# robot_vr.net
KiCad netlist of a schematic drawn in EAGLE
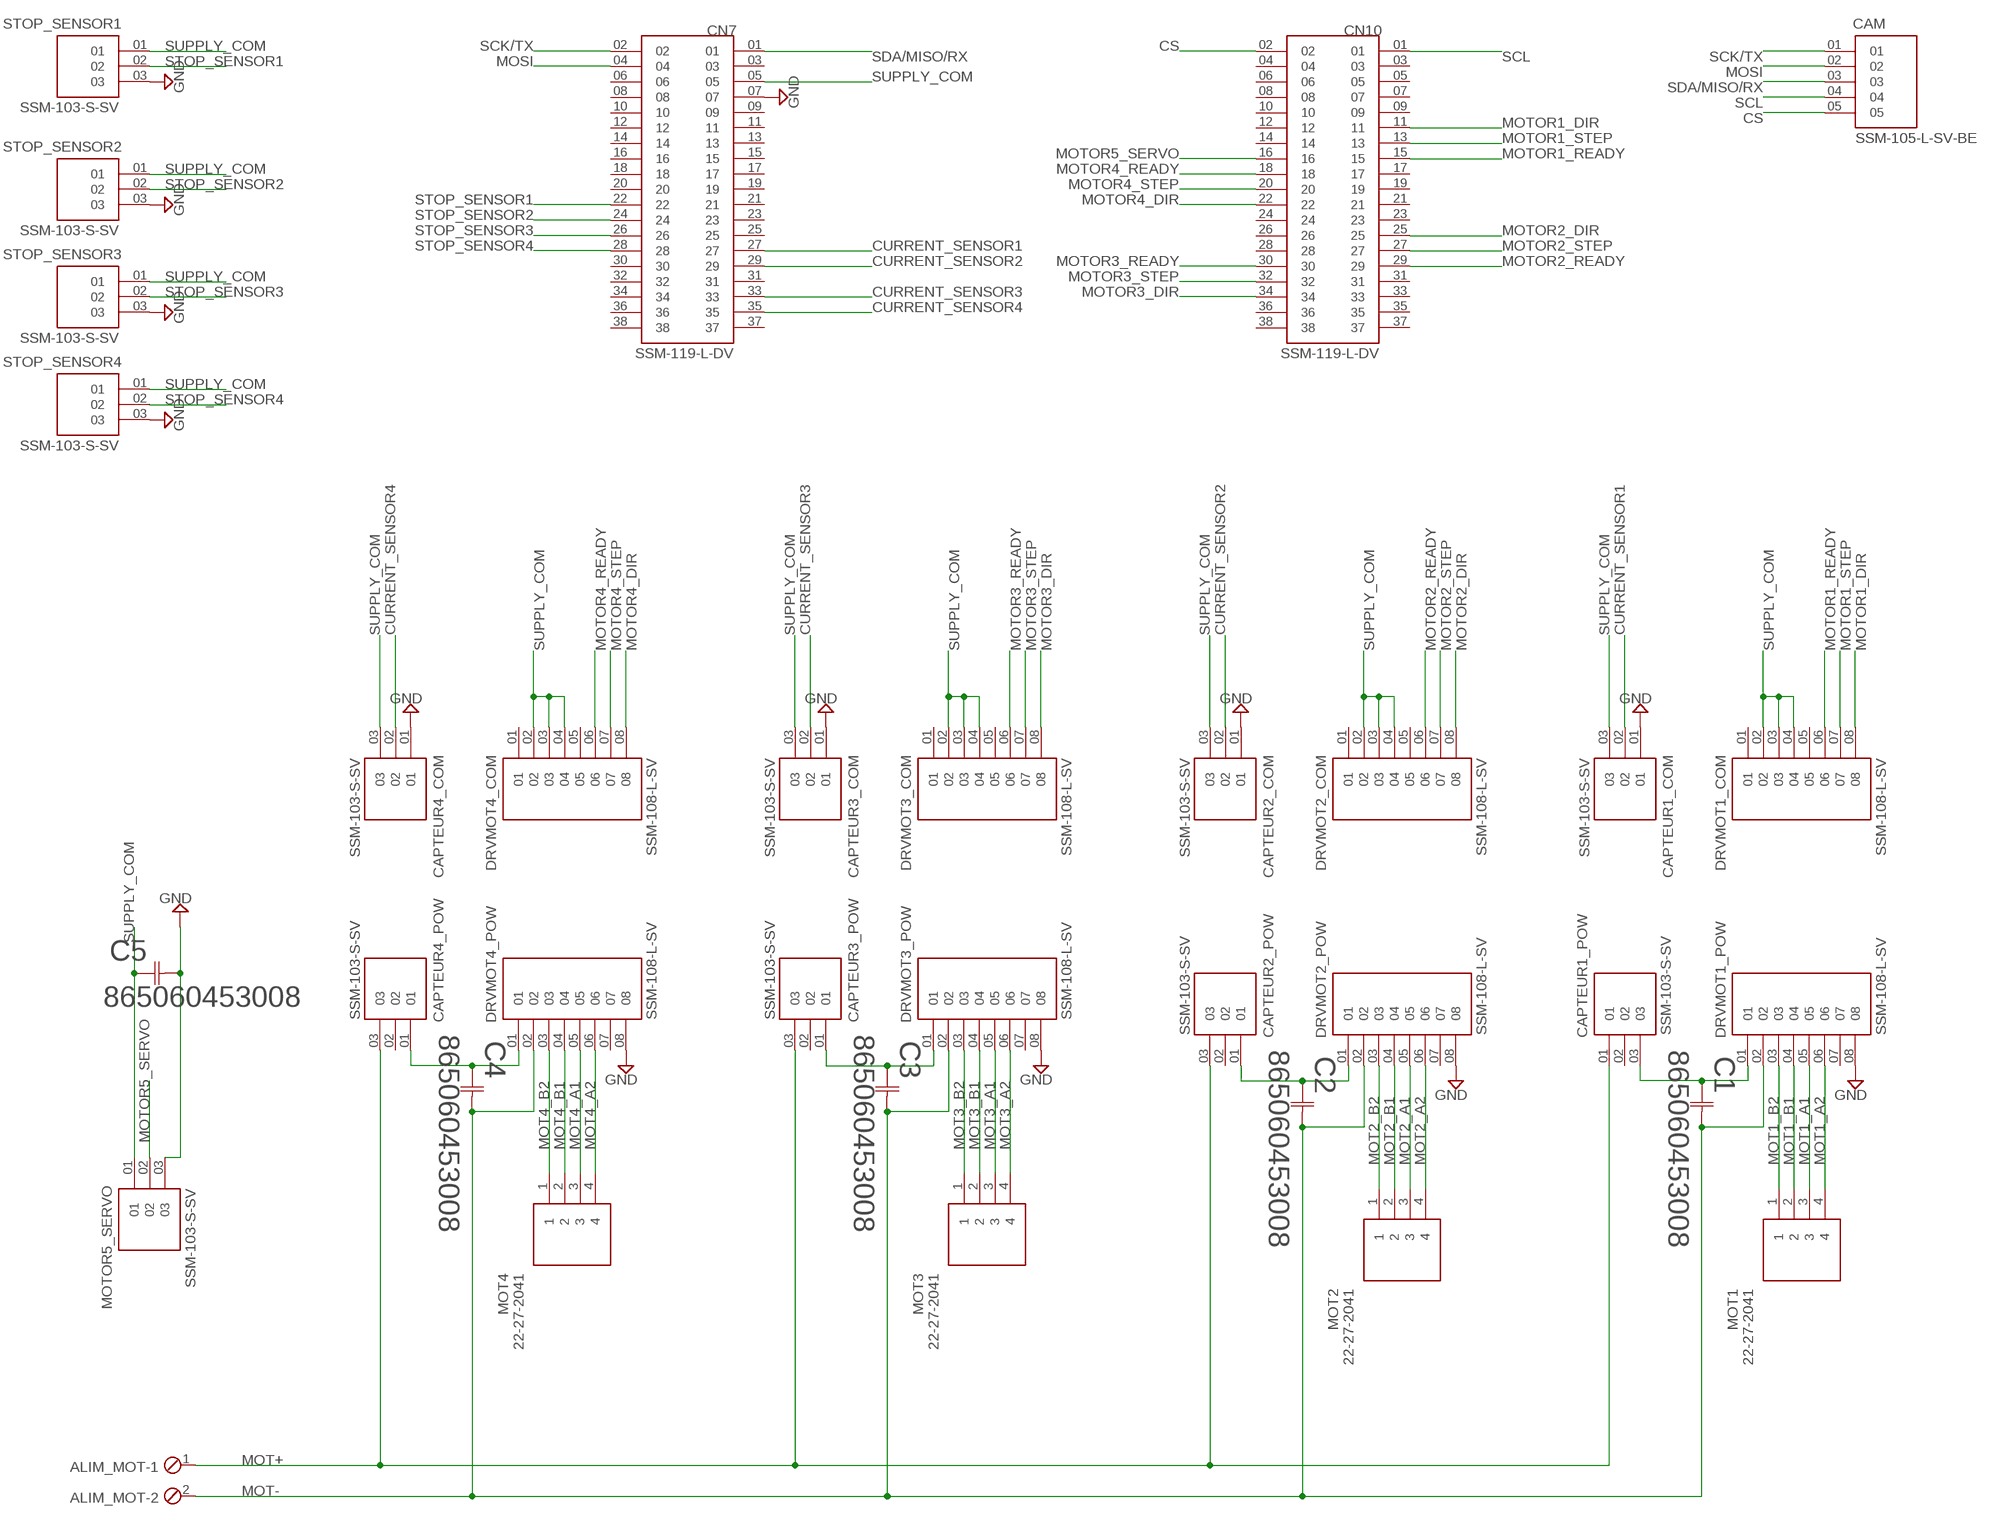
[diagram p0: schematic, sheet 1]

(export (version "E")
  (design (tool "Eeschema 10.0.6"))
  (components
    (comp (ref "ALIM_MOT")
      (value "MPT2")
      (footprint "eagle-import:2POL254")
      (libsource (lib "eagle-import") (part "MPT2"))
    )
    (comp (ref "C1")
      (value "865060453008")
      (footprint "eagle-import:CAP_865060453008_WRE")
      (fields (field (name "COPYRIGHT") "Copyright (C) 2022 Ultra Librarian. All rights reserved."))
      (libsource (lib "eagle-import") (part "865060453008"))
    )
    (comp (ref "C2")
      (value "865060453008")
      (footprint "eagle-import:CAP_865060453008_WRE")
      (fields (field (name "COPYRIGHT") "Copyright (C) 2022 Ultra Librarian. All rights reserved."))
      (libsource (lib "eagle-import") (part "865060453008"))
    )
    (comp (ref "C3")
      (value "865060453008")
      (footprint "eagle-import:CAP_865060453008_WRE")
      (fields (field (name "COPYRIGHT") "Copyright (C) 2022 Ultra Librarian. All rights reserved."))
      (libsource (lib "eagle-import") (part "865060453008"))
    )
    (comp (ref "C4")
      (value "865060453008")
      (footprint "eagle-import:CAP_865060453008_WRE")
      (fields (field (name "COPYRIGHT") "Copyright (C) 2022 Ultra Librarian. All rights reserved."))
      (libsource (lib "eagle-import") (part "865060453008"))
    )
    (comp (ref "C5")
      (value "865060453008")
      (footprint "eagle-import:CAP_865060453008_WRE")
      (fields (field (name "COPYRIGHT") "Copyright (C) 2022 Ultra Librarian. All rights reserved."))
      (libsource (lib "eagle-import") (part "865060453008"))
    )
    (comp (ref "CAM")
      (value "SSM-105-L-SV-BE")
      (footprint "eagle-import:SAMTEC_SSM-105-L-SV-BE")
      (fields (field (name "MF") "Samtec") (field (name "MP") "SSM-105-L-SV-BE-TR"))
      (libsource (lib "eagle-import") (part "SSM-105-L-SV-BE"))
    )
    (comp (ref "CAPTEUR1_COM")
      (value "SSM-103-S-SV")
      (footprint "eagle-import:SAMTEC_SSM-103-S-SV")
      (fields (field (name "MF") "Samtec"))
      (libsource (lib "eagle-import") (part "SSM-103-S-SV"))
    )
    (comp (ref "CAPTEUR1_POW")
      (value "SSM-103-S-SV")
      (footprint "eagle-import:SAMTEC_SSM-103-S-SV")
      (fields (field (name "MF") "Samtec"))
      (libsource (lib "eagle-import") (part "SSM-103-S-SV"))
    )
    (comp (ref "CAPTEUR2_COM")
      (value "SSM-103-S-SV")
      (footprint "eagle-import:SAMTEC_SSM-103-S-SV")
      (fields (field (name "MF") "Samtec"))
      (libsource (lib "eagle-import") (part "SSM-103-S-SV"))
    )
    (comp (ref "CAPTEUR2_POW")
      (value "SSM-103-S-SV")
      (footprint "eagle-import:SAMTEC_SSM-103-S-SV")
      (fields (field (name "MF") "Samtec"))
      (libsource (lib "eagle-import") (part "SSM-103-S-SV"))
    )
    (comp (ref "CAPTEUR3_COM")
      (value "SSM-103-S-SV")
      (footprint "eagle-import:SAMTEC_SSM-103-S-SV")
      (fields (field (name "MF") "Samtec"))
      (libsource (lib "eagle-import") (part "SSM-103-S-SV"))
    )
    (comp (ref "CAPTEUR3_POW")
      (value "SSM-103-S-SV")
      (footprint "eagle-import:SAMTEC_SSM-103-S-SV")
      (fields (field (name "MF") "Samtec"))
      (libsource (lib "eagle-import") (part "SSM-103-S-SV"))
    )
    (comp (ref "CAPTEUR4_COM")
      (value "SSM-103-S-SV")
      (footprint "eagle-import:SAMTEC_SSM-103-S-SV")
      (fields (field (name "MF") "Samtec"))
      (libsource (lib "eagle-import") (part "SSM-103-S-SV"))
    )
    (comp (ref "CAPTEUR4_POW")
      (value "SSM-103-S-SV")
      (footprint "eagle-import:SAMTEC_SSM-103-S-SV")
      (fields (field (name "MF") "Samtec"))
      (libsource (lib "eagle-import") (part "SSM-103-S-SV"))
    )
    (comp (ref "CN7")
      (value "SSM-119-L-DV")
      (footprint "eagle-import:SAMTEC_SSM-119-L-DV")
      (fields (field (name "MF") "Samtec Inc."))
      (libsource (lib "eagle-import") (part "SSM-119-L-DV"))
    )
    (comp (ref "CN10")
      (value "SSM-119-L-DV")
      (footprint "eagle-import:SAMTEC_SSM-119-L-DV")
      (fields (field (name "MF") "Samtec Inc."))
      (libsource (lib "eagle-import") (part "SSM-119-L-DV"))
    )
    (comp (ref "DRVMOT1_COM")
      (value "SSM-108-L-SV")
      (footprint "eagle-import:SAMTEC_SSM-108-L-SV")
      (fields (field (name "MF") "Samtec"))
      (libsource (lib "eagle-import") (part "SSM-108-L-SV"))
    )
    (comp (ref "DRVMOT1_POW")
      (value "SSM-108-L-SV")
      (footprint "eagle-import:SAMTEC_SSM-108-L-SV")
      (fields (field (name "MF") "Samtec"))
      (libsource (lib "eagle-import") (part "SSM-108-L-SV"))
    )
    (comp (ref "DRVMOT2_COM")
      (value "SSM-108-L-SV")
      (footprint "eagle-import:SAMTEC_SSM-108-L-SV")
      (fields (field (name "MF") "Samtec"))
      (libsource (lib "eagle-import") (part "SSM-108-L-SV"))
    )
    (comp (ref "DRVMOT2_POW")
      (value "SSM-108-L-SV")
      (footprint "eagle-import:SAMTEC_SSM-108-L-SV")
      (fields (field (name "MF") "Samtec"))
      (libsource (lib "eagle-import") (part "SSM-108-L-SV"))
    )
    (comp (ref "DRVMOT3_COM")
      (value "SSM-108-L-SV")
      (footprint "eagle-import:SAMTEC_SSM-108-L-SV")
      (fields (field (name "MF") "Samtec"))
      (libsource (lib "eagle-import") (part "SSM-108-L-SV"))
    )
    (comp (ref "DRVMOT3_POW")
      (value "SSM-108-L-SV")
      (footprint "eagle-import:SAMTEC_SSM-108-L-SV")
      (fields (field (name "MF") "Samtec"))
      (libsource (lib "eagle-import") (part "SSM-108-L-SV"))
    )
    (comp (ref "DRVMOT4_COM")
      (value "SSM-108-L-SV")
      (footprint "eagle-import:SAMTEC_SSM-108-L-SV")
      (fields (field (name "MF") "Samtec"))
      (libsource (lib "eagle-import") (part "SSM-108-L-SV"))
    )
    (comp (ref "DRVMOT4_POW")
      (value "SSM-108-L-SV")
      (footprint "eagle-import:SAMTEC_SSM-108-L-SV")
      (fields (field (name "MF") "Samtec"))
      (libsource (lib "eagle-import") (part "SSM-108-L-SV"))
    )
    (comp (ref "MOT1")
      (value "22-27-2041")
      (footprint "eagle-import:HDRV4W64P254_100_4X1_1016X580H")
      (libsource (lib "eagle-import") (part "22-27-2041"))
    )
    (comp (ref "MOT2")
      (value "22-27-2041")
      (footprint "eagle-import:HDRV4W64P254_100_4X1_1016X580H")
      (libsource (lib "eagle-import") (part "22-27-2041"))
    )
    (comp (ref "MOT3")
      (value "22-27-2041")
      (footprint "eagle-import:HDRV4W64P254_100_4X1_1016X580H")
      (libsource (lib "eagle-import") (part "22-27-2041"))
    )
    (comp (ref "MOT4")
      (value "22-27-2041")
      (footprint "eagle-import:HDRV4W64P254_100_4X1_1016X580H")
      (libsource (lib "eagle-import") (part "22-27-2041"))
    )
    (comp (ref "MOTOR5_SERVO")
      (value "SSM-103-S-SV")
      (footprint "eagle-import:SAMTEC_SSM-103-S-SV")
      (fields (field (name "MF") "Samtec"))
      (libsource (lib "eagle-import") (part "SSM-103-S-SV"))
    )
    (comp (ref "STOP_SENSOR1")
      (value "SSM-103-S-SV")
      (footprint "eagle-import:SAMTEC_SSM-103-S-SV")
      (fields (field (name "MF") "Samtec"))
      (libsource (lib "eagle-import") (part "SSM-103-S-SV"))
    )
    (comp (ref "STOP_SENSOR2")
      (value "SSM-103-S-SV")
      (footprint "eagle-import:SAMTEC_SSM-103-S-SV")
      (fields (field (name "MF") "Samtec"))
      (libsource (lib "eagle-import") (part "SSM-103-S-SV"))
    )
    (comp (ref "STOP_SENSOR3")
      (value "SSM-103-S-SV")
      (footprint "eagle-import:SAMTEC_SSM-103-S-SV")
      (fields (field (name "MF") "Samtec"))
      (libsource (lib "eagle-import") (part "SSM-103-S-SV"))
    )
    (comp (ref "STOP_SENSOR4")
      (value "SSM-103-S-SV")
      (footprint "eagle-import:SAMTEC_SSM-103-S-SV")
      (fields (field (name "MF") "Samtec"))
      (libsource (lib "eagle-import") (part "SSM-103-S-SV"))
    )
  )
  (nets
    (net (code "1") (name "/CS") (class "Default")
      (node (ref "CAM") (pin "05") (pinfunction "05_05") (pintype "passive"))
      (node (ref "CN10") (pin "02") (pinfunction "02_02") (pintype "passive"))
    )
    (net (code "2") (name "/CURRENT_SENSOR1") (class "Default")
      (node (ref "CAPTEUR1_COM") (pin "02") (pinfunction "02_02") (pintype "passive"))
      (node (ref "CN7") (pin "27") (pinfunction "27_27") (pintype "passive"))
    )
    (net (code "3") (name "/CURRENT_SENSOR2") (class "Default")
      (node (ref "CAPTEUR2_COM") (pin "02") (pinfunction "02_02") (pintype "passive"))
      (node (ref "CN7") (pin "29") (pinfunction "29_29") (pintype "passive"))
    )
    (net (code "4") (name "/CURRENT_SENSOR3") (class "Default")
      (node (ref "CAPTEUR3_COM") (pin "02") (pinfunction "02_02") (pintype "passive"))
      (node (ref "CN7") (pin "33") (pinfunction "33_33") (pintype "passive"))
    )
    (net (code "5") (name "/CURRENT_SENSOR4") (class "Default")
      (node (ref "CAPTEUR4_COM") (pin "02") (pinfunction "02_02") (pintype "passive"))
      (node (ref "CN7") (pin "35") (pinfunction "35_35") (pintype "passive"))
    )
    (net (code "6") (name "/MOSI") (class "Default")
      (node (ref "CAM") (pin "02") (pinfunction "02_02") (pintype "passive"))
      (node (ref "CN7") (pin "04") (pinfunction "04_04") (pintype "passive"))
    )
    (net (code "7") (name "/MOT+") (class "Default")
      (node (ref "ALIM_MOT") (pin "1") (pinfunction "1_1") (pintype "passive"))
      (node (ref "CAPTEUR1_POW") (pin "01") (pinfunction "01_01") (pintype "passive"))
      (node (ref "CAPTEUR2_POW") (pin "03") (pinfunction "03_03") (pintype "passive"))
      (node (ref "CAPTEUR3_POW") (pin "03") (pinfunction "03_03") (pintype "passive"))
      (node (ref "CAPTEUR4_POW") (pin "03") (pinfunction "03_03") (pintype "passive"))
    )
    (net (code "8") (name "/MOT-") (class "Default")
      (node (ref "ALIM_MOT") (pin "2") (pinfunction "1_2") (pintype "passive"))
      (node (ref "C1") (pin "2") (pinfunction "2_2") (pintype "passive"))
      (node (ref "C2") (pin "2") (pinfunction "2_2") (pintype "passive"))
      (node (ref "C3") (pin "2") (pinfunction "2_2") (pintype "passive"))
      (node (ref "C4") (pin "2") (pinfunction "2_2") (pintype "passive"))
      (node (ref "DRVMOT1_POW") (pin "02") (pinfunction "02_02") (pintype "passive"))
      (node (ref "DRVMOT2_POW") (pin "02") (pinfunction "02_02") (pintype "passive"))
      (node (ref "DRVMOT3_POW") (pin "02") (pinfunction "02_02") (pintype "passive"))
      (node (ref "DRVMOT4_POW") (pin "02") (pinfunction "02_02") (pintype "passive"))
    )
    (net (code "9") (name "/MOT1_A1") (class "Default")
      (node (ref "DRVMOT1_POW") (pin "05") (pinfunction "05_05") (pintype "passive"))
      (node (ref "MOT1") (pin "3") (pinfunction "3_3") (pintype "bidirectional"))
    )
    (net (code "10") (name "/MOT1_A2") (class "Default")
      (node (ref "DRVMOT1_POW") (pin "06") (pinfunction "06_06") (pintype "passive"))
      (node (ref "MOT1") (pin "4") (pinfunction "4_4") (pintype "bidirectional"))
    )
    (net (code "11") (name "/MOT1_B1") (class "Default")
      (node (ref "DRVMOT1_POW") (pin "04") (pinfunction "04_04") (pintype "passive"))
      (node (ref "MOT1") (pin "2") (pinfunction "2_2") (pintype "bidirectional"))
    )
    (net (code "12") (name "/MOT1_B2") (class "Default")
      (node (ref "DRVMOT1_POW") (pin "03") (pinfunction "03_03") (pintype "passive"))
      (node (ref "MOT1") (pin "1") (pinfunction "1_1") (pintype "bidirectional"))
    )
    (net (code "13") (name "/MOT2_A1") (class "Default")
      (node (ref "DRVMOT2_POW") (pin "05") (pinfunction "05_05") (pintype "passive"))
      (node (ref "MOT2") (pin "3") (pinfunction "3_3") (pintype "bidirectional"))
    )
    (net (code "14") (name "/MOT2_A2") (class "Default")
      (node (ref "DRVMOT2_POW") (pin "06") (pinfunction "06_06") (pintype "passive"))
      (node (ref "MOT2") (pin "4") (pinfunction "4_4") (pintype "bidirectional"))
    )
    (net (code "15") (name "/MOT2_B1") (class "Default")
      (node (ref "DRVMOT2_POW") (pin "04") (pinfunction "04_04") (pintype "passive"))
      (node (ref "MOT2") (pin "2") (pinfunction "2_2") (pintype "bidirectional"))
    )
    (net (code "16") (name "/MOT2_B2") (class "Default")
      (node (ref "DRVMOT2_POW") (pin "03") (pinfunction "03_03") (pintype "passive"))
      (node (ref "MOT2") (pin "1") (pinfunction "1_1") (pintype "bidirectional"))
    )
    (net (code "17") (name "/MOT3_A1") (class "Default")
      (node (ref "DRVMOT3_POW") (pin "05") (pinfunction "05_05") (pintype "passive"))
      (node (ref "MOT3") (pin "3") (pinfunction "3_3") (pintype "bidirectional"))
    )
    (net (code "18") (name "/MOT3_A2") (class "Default")
      (node (ref "DRVMOT3_POW") (pin "06") (pinfunction "06_06") (pintype "passive"))
      (node (ref "MOT3") (pin "4") (pinfunction "4_4") (pintype "bidirectional"))
    )
    (net (code "19") (name "/MOT3_B1") (class "Default")
      (node (ref "DRVMOT3_POW") (pin "04") (pinfunction "04_04") (pintype "passive"))
      (node (ref "MOT3") (pin "2") (pinfunction "2_2") (pintype "bidirectional"))
    )
    (net (code "20") (name "/MOT3_B2") (class "Default")
      (node (ref "DRVMOT3_POW") (pin "03") (pinfunction "03_03") (pintype "passive"))
      (node (ref "MOT3") (pin "1") (pinfunction "1_1") (pintype "bidirectional"))
    )
    (net (code "21") (name "/MOT4_A1") (class "Default")
      (node (ref "DRVMOT4_POW") (pin "05") (pinfunction "05_05") (pintype "passive"))
      (node (ref "MOT4") (pin "3") (pinfunction "3_3") (pintype "bidirectional"))
    )
    (net (code "22") (name "/MOT4_A2") (class "Default")
      (node (ref "DRVMOT4_POW") (pin "06") (pinfunction "06_06") (pintype "passive"))
      (node (ref "MOT4") (pin "4") (pinfunction "4_4") (pintype "bidirectional"))
    )
    (net (code "23") (name "/MOT4_B1") (class "Default")
      (node (ref "DRVMOT4_POW") (pin "04") (pinfunction "04_04") (pintype "passive"))
      (node (ref "MOT4") (pin "2") (pinfunction "2_2") (pintype "bidirectional"))
    )
    (net (code "24") (name "/MOT4_B2") (class "Default")
      (node (ref "DRVMOT4_POW") (pin "03") (pinfunction "03_03") (pintype "passive"))
      (node (ref "MOT4") (pin "1") (pinfunction "1_1") (pintype "bidirectional"))
    )
    (net (code "25") (name "/MOTOR1_DIR") (class "Default")
      (node (ref "CN10") (pin "11") (pinfunction "11_11") (pintype "passive"))
      (node (ref "DRVMOT1_COM") (pin "08") (pinfunction "08_08") (pintype "passive"))
    )
    (net (code "26") (name "/MOTOR1_READY") (class "Default")
      (node (ref "CN10") (pin "15") (pinfunction "15_15") (pintype "passive"))
      (node (ref "DRVMOT1_COM") (pin "06") (pinfunction "06_06") (pintype "passive"))
    )
    (net (code "27") (name "/MOTOR1_STEP") (class "Default")
      (node (ref "CN10") (pin "13") (pinfunction "13_13") (pintype "passive"))
      (node (ref "DRVMOT1_COM") (pin "07") (pinfunction "07_07") (pintype "passive"))
    )
    (net (code "28") (name "/MOTOR2_DIR") (class "Default")
      (node (ref "CN10") (pin "25") (pinfunction "25_25") (pintype "passive"))
      (node (ref "DRVMOT2_COM") (pin "08") (pinfunction "08_08") (pintype "passive"))
    )
    (net (code "29") (name "/MOTOR2_READY") (class "Default")
      (node (ref "CN10") (pin "29") (pinfunction "29_29") (pintype "passive"))
      (node (ref "DRVMOT2_COM") (pin "06") (pinfunction "06_06") (pintype "passive"))
    )
    (net (code "30") (name "/MOTOR2_STEP") (class "Default")
      (node (ref "CN10") (pin "27") (pinfunction "27_27") (pintype "passive"))
      (node (ref "DRVMOT2_COM") (pin "07") (pinfunction "07_07") (pintype "passive"))
    )
    (net (code "31") (name "/MOTOR3_DIR") (class "Default")
      (node (ref "CN10") (pin "34") (pinfunction "34_34") (pintype "passive"))
      (node (ref "DRVMOT3_COM") (pin "08") (pinfunction "08_08") (pintype "passive"))
    )
    (net (code "32") (name "/MOTOR3_READY") (class "Default")
      (node (ref "CN10") (pin "30") (pinfunction "30_30") (pintype "passive"))
      (node (ref "DRVMOT3_COM") (pin "06") (pinfunction "06_06") (pintype "passive"))
    )
    (net (code "33") (name "/MOTOR3_STEP") (class "Default")
      (node (ref "CN10") (pin "32") (pinfunction "32_32") (pintype "passive"))
      (node (ref "DRVMOT3_COM") (pin "07") (pinfunction "07_07") (pintype "passive"))
    )
    (net (code "34") (name "/MOTOR4_DIR") (class "Default")
      (node (ref "CN10") (pin "22") (pinfunction "22_22") (pintype "passive"))
      (node (ref "DRVMOT4_COM") (pin "08") (pinfunction "08_08") (pintype "passive"))
    )
    (net (code "35") (name "/MOTOR4_READY") (class "Default")
      (node (ref "CN10") (pin "18") (pinfunction "18_18") (pintype "passive"))
      (node (ref "DRVMOT4_COM") (pin "06") (pinfunction "06_06") (pintype "passive"))
    )
    (net (code "36") (name "/MOTOR4_STEP") (class "Default")
      (node (ref "CN10") (pin "20") (pinfunction "20_20") (pintype "passive"))
      (node (ref "DRVMOT4_COM") (pin "07") (pinfunction "07_07") (pintype "passive"))
    )
    (net (code "37") (name "/MOTOR5_SERVO") (class "Default")
      (node (ref "CN10") (pin "16") (pinfunction "16_16") (pintype "passive"))
      (node (ref "MOTOR5_SERVO") (pin "02") (pinfunction "02_02") (pintype "passive"))
    )
    (net (code "38") (name "/SCK{slash}TX") (class "Default")
      (node (ref "CAM") (pin "01") (pinfunction "01_01") (pintype "passive"))
      (node (ref "CN7") (pin "02") (pinfunction "02_02") (pintype "passive"))
    )
    (net (code "39") (name "/SCL") (class "Default")
      (node (ref "CAM") (pin "04") (pinfunction "04_04") (pintype "passive"))
      (node (ref "CN10") (pin "01") (pinfunction "01_01") (pintype "passive"))
    )
    (net (code "40") (name "/SDA{slash}MISO{slash}RX") (class "Default")
      (node (ref "CAM") (pin "03") (pinfunction "03_03") (pintype "passive"))
      (node (ref "CN7") (pin "01") (pinfunction "01_01") (pintype "passive"))
    )
    (net (code "41") (name "/STOP_SENSOR1") (class "Default")
      (node (ref "CN7") (pin "22") (pinfunction "22_22") (pintype "passive"))
      (node (ref "STOP_SENSOR1") (pin "02") (pinfunction "02_02") (pintype "passive"))
    )
    (net (code "42") (name "/STOP_SENSOR2") (class "Default")
      (node (ref "CN7") (pin "24") (pinfunction "24_24") (pintype "passive"))
      (node (ref "STOP_SENSOR2") (pin "02") (pinfunction "02_02") (pintype "passive"))
    )
    (net (code "43") (name "/STOP_SENSOR3") (class "Default")
      (node (ref "CN7") (pin "26") (pinfunction "26_26") (pintype "passive"))
      (node (ref "STOP_SENSOR3") (pin "02") (pinfunction "02_02") (pintype "passive"))
    )
    (net (code "44") (name "/STOP_SENSOR4") (class "Default")
      (node (ref "CN7") (pin "28") (pinfunction "28_28") (pintype "passive"))
      (node (ref "STOP_SENSOR4") (pin "02") (pinfunction "02_02") (pintype "passive"))
    )
    (net (code "45") (name "/SUPPLY_COM") (class "Default")
      (node (ref "C5") (pin "1") (pinfunction "1_1") (pintype "passive"))
      (node (ref "CAPTEUR1_COM") (pin "03") (pinfunction "03_03") (pintype "passive"))
      (node (ref "CAPTEUR2_COM") (pin "03") (pinfunction "03_03") (pintype "passive"))
      (node (ref "CAPTEUR3_COM") (pin "03") (pinfunction "03_03") (pintype "passive"))
      (node (ref "CAPTEUR4_COM") (pin "03") (pinfunction "03_03") (pintype "passive"))
      (node (ref "CN7") (pin "05") (pinfunction "05_05") (pintype "passive"))
      (node (ref "DRVMOT1_COM") (pin "02") (pinfunction "02_02") (pintype "passive"))
      (node (ref "DRVMOT1_COM") (pin "03") (pinfunction "03_03") (pintype "passive"))
      (node (ref "DRVMOT1_COM") (pin "04") (pinfunction "04_04") (pintype "passive"))
      (node (ref "DRVMOT2_COM") (pin "02") (pinfunction "02_02") (pintype "passive"))
      (node (ref "DRVMOT2_COM") (pin "03") (pinfunction "03_03") (pintype "passive"))
      (node (ref "DRVMOT2_COM") (pin "04") (pinfunction "04_04") (pintype "passive"))
      (node (ref "DRVMOT3_COM") (pin "02") (pinfunction "02_02") (pintype "passive"))
      (node (ref "DRVMOT3_COM") (pin "03") (pinfunction "03_03") (pintype "passive"))
      (node (ref "DRVMOT3_COM") (pin "04") (pinfunction "04_04") (pintype "passive"))
      (node (ref "DRVMOT4_COM") (pin "02") (pinfunction "02_02") (pintype "passive"))
      (node (ref "DRVMOT4_COM") (pin "03") (pinfunction "03_03") (pintype "passive"))
      (node (ref "DRVMOT4_COM") (pin "04") (pinfunction "04_04") (pintype "passive"))
      (node (ref "MOTOR5_SERVO") (pin "01") (pinfunction "01_01") (pintype "passive"))
      (node (ref "STOP_SENSOR1") (pin "01") (pinfunction "01_01") (pintype "passive"))
      (node (ref "STOP_SENSOR2") (pin "01") (pinfunction "01_01") (pintype "passive"))
      (node (ref "STOP_SENSOR3") (pin "01") (pinfunction "01_01") (pintype "passive"))
      (node (ref "STOP_SENSOR4") (pin "01") (pinfunction "01_01") (pintype "passive"))
    )
    (net (code "46") (name "GND") (class "Default")
      (node (ref "C5") (pin "2") (pinfunction "2_2") (pintype "passive"))
      (node (ref "CAPTEUR1_COM") (pin "01") (pinfunction "01_01") (pintype "passive"))
      (node (ref "CAPTEUR2_COM") (pin "01") (pinfunction "01_01") (pintype "passive"))
      (node (ref "CAPTEUR3_COM") (pin "01") (pinfunction "01_01") (pintype "passive"))
      (node (ref "CAPTEUR4_COM") (pin "01") (pinfunction "01_01") (pintype "passive"))
      (node (ref "CN7") (pin "07") (pinfunction "07_07") (pintype "passive"))
      (node (ref "DRVMOT1_POW") (pin "08") (pinfunction "08_08") (pintype "passive"))
      (node (ref "DRVMOT2_POW") (pin "08") (pinfunction "08_08") (pintype "passive"))
      (node (ref "DRVMOT3_POW") (pin "08") (pinfunction "08_08") (pintype "passive"))
      (node (ref "DRVMOT4_POW") (pin "08") (pinfunction "08_08") (pintype "passive"))
      (node (ref "MOTOR5_SERVO") (pin "03") (pinfunction "03_03") (pintype "passive"))
      (node (ref "STOP_SENSOR1") (pin "03") (pinfunction "03_03") (pintype "passive"))
      (node (ref "STOP_SENSOR2") (pin "03") (pinfunction "03_03") (pintype "passive"))
      (node (ref "STOP_SENSOR3") (pin "03") (pinfunction "03_03") (pintype "passive"))
      (node (ref "STOP_SENSOR4") (pin "03") (pinfunction "03_03") (pintype "passive"))
    )
    (net (code "47") (name "Net-(C1-Pad1)") (class "Default")
      (node (ref "C1") (pin "1") (pinfunction "1_1") (pintype "passive"))
      (node (ref "CAPTEUR1_POW") (pin "03") (pinfunction "03_03") (pintype "passive"))
      (node (ref "DRVMOT1_POW") (pin "01") (pinfunction "01_01") (pintype "passive"))
    )
    (net (code "48") (name "Net-(C2-Pad1)") (class "Default")
      (node (ref "C2") (pin "1") (pinfunction "1_1") (pintype "passive"))
      (node (ref "CAPTEUR2_POW") (pin "01") (pinfunction "01_01") (pintype "passive"))
      (node (ref "DRVMOT2_POW") (pin "01") (pinfunction "01_01") (pintype "passive"))
    )
    (net (code "49") (name "Net-(C3-Pad1)") (class "Default")
      (node (ref "C3") (pin "1") (pinfunction "1_1") (pintype "passive"))
      (node (ref "CAPTEUR3_POW") (pin "01") (pinfunction "01_01") (pintype "passive"))
      (node (ref "DRVMOT3_POW") (pin "01") (pinfunction "01_01") (pintype "passive"))
    )
    (net (code "50") (name "Net-(C4-Pad1)") (class "Default")
      (node (ref "C4") (pin "1") (pinfunction "1_1") (pintype "passive"))
      (node (ref "CAPTEUR4_POW") (pin "01") (pinfunction "01_01") (pintype "passive"))
      (node (ref "DRVMOT4_POW") (pin "01") (pinfunction "01_01") (pintype "passive"))
    )
    (net (code "51") (name "unconnected-(CAPTEUR1_POW-Pad02)") (class "Default")
      (node (ref "CAPTEUR1_POW") (pin "02") (pinfunction "02_02") (pintype "passive"))
    )
    (net (code "52") (name "unconnected-(CAPTEUR2_POW-Pad02)") (class "Default")
      (node (ref "CAPTEUR2_POW") (pin "02") (pinfunction "02_02") (pintype "passive"))
    )
    (net (code "53") (name "unconnected-(CAPTEUR3_POW-Pad02)") (class "Default")
      (node (ref "CAPTEUR3_POW") (pin "02") (pinfunction "02_02") (pintype "passive"))
    )
    (net (code "54") (name "unconnected-(CAPTEUR4_POW-Pad02)") (class "Default")
      (node (ref "CAPTEUR4_POW") (pin "02") (pinfunction "02_02") (pintype "passive"))
    )
    (net (code "55") (name "unconnected-(CN7-Pad03)") (class "Default")
      (node (ref "CN7") (pin "03") (pinfunction "03_03") (pintype "passive"))
    )
    (net (code "56") (name "unconnected-(CN7-Pad06)") (class "Default")
      (node (ref "CN7") (pin "06") (pinfunction "06_06") (pintype "passive"))
    )
    (net (code "57") (name "unconnected-(CN7-Pad08)") (class "Default")
      (node (ref "CN7") (pin "08") (pinfunction "08_08") (pintype "passive"))
    )
    (net (code "58") (name "unconnected-(CN7-Pad09)") (class "Default")
      (node (ref "CN7") (pin "09") (pinfunction "09_09") (pintype "passive"))
    )
    (net (code "59") (name "unconnected-(CN7-Pad10)") (class "Default")
      (node (ref "CN7") (pin "10") (pinfunction "10_10") (pintype "passive"))
    )
    (net (code "60") (name "unconnected-(CN7-Pad11)") (class "Default")
      (node (ref "CN7") (pin "11") (pinfunction "11_11") (pintype "passive"))
    )
    (net (code "61") (name "unconnected-(CN7-Pad12)") (class "Default")
      (node (ref "CN7") (pin "12") (pinfunction "12_12") (pintype "passive"))
    )
    (net (code "62") (name "unconnected-(CN7-Pad13)") (class "Default")
      (node (ref "CN7") (pin "13") (pinfunction "13_13") (pintype "passive"))
    )
    (net (code "63") (name "unconnected-(CN7-Pad14)") (class "Default")
      (node (ref "CN7") (pin "14") (pinfunction "14_14") (pintype "passive"))
    )
    (net (code "64") (name "unconnected-(CN7-Pad15)") (class "Default")
      (node (ref "CN7") (pin "15") (pinfunction "15_15") (pintype "passive"))
    )
    (net (code "65") (name "unconnected-(CN7-Pad16)") (class "Default")
      (node (ref "CN7") (pin "16") (pinfunction "16_16") (pintype "passive"))
    )
    (net (code "66") (name "unconnected-(CN7-Pad17)") (class "Default")
      (node (ref "CN7") (pin "17") (pinfunction "17_17") (pintype "passive"))
    )
    (net (code "67") (name "unconnected-(CN7-Pad18)") (class "Default")
      (node (ref "CN7") (pin "18") (pinfunction "18_18") (pintype "passive"))
    )
    (net (code "68") (name "unconnected-(CN7-Pad19)") (class "Default")
      (node (ref "CN7") (pin "19") (pinfunction "19_19") (pintype "passive"))
    )
    (net (code "69") (name "unconnected-(CN7-Pad20)") (class "Default")
      (node (ref "CN7") (pin "20") (pinfunction "20_20") (pintype "passive"))
    )
    (net (code "70") (name "unconnected-(CN7-Pad21)") (class "Default")
      (node (ref "CN7") (pin "21") (pinfunction "21_21") (pintype "passive"))
    )
    (net (code "71") (name "unconnected-(CN7-Pad23)") (class "Default")
      (node (ref "CN7") (pin "23") (pinfunction "23_23") (pintype "passive"))
    )
    (net (code "72") (name "unconnected-(CN7-Pad25)") (class "Default")
      (node (ref "CN7") (pin "25") (pinfunction "25_25") (pintype "passive"))
    )
    (net (code "73") (name "unconnected-(CN7-Pad30)") (class "Default")
      (node (ref "CN7") (pin "30") (pinfunction "30_30") (pintype "passive"))
    )
    (net (code "74") (name "unconnected-(CN7-Pad31)") (class "Default")
      (node (ref "CN7") (pin "31") (pinfunction "31_31") (pintype "passive"))
    )
    (net (code "75") (name "unconnected-(CN7-Pad32)") (class "Default")
      (node (ref "CN7") (pin "32") (pinfunction "32_32") (pintype "passive"))
    )
    (net (code "76") (name "unconnected-(CN7-Pad34)") (class "Default")
      (node (ref "CN7") (pin "34") (pinfunction "34_34") (pintype "passive"))
    )
    (net (code "77") (name "unconnected-(CN7-Pad36)") (class "Default")
      (node (ref "CN7") (pin "36") (pinfunction "36_36") (pintype "passive"))
    )
    (net (code "78") (name "unconnected-(CN7-Pad37)") (class "Default")
      (node (ref "CN7") (pin "37") (pinfunction "37_37") (pintype "passive"))
    )
    (net (code "79") (name "unconnected-(CN7-Pad38)") (class "Default")
      (node (ref "CN7") (pin "38") (pinfunction "38_38") (pintype "passive"))
    )
    (net (code "80") (name "unconnected-(CN10-Pad03)") (class "Default")
      (node (ref "CN10") (pin "03") (pinfunction "03_03") (pintype "passive"))
    )
    (net (code "81") (name "unconnected-(CN10-Pad04)") (class "Default")
      (node (ref "CN10") (pin "04") (pinfunction "04_04") (pintype "passive"))
    )
    (net (code "82") (name "unconnected-(CN10-Pad05)") (class "Default")
      (node (ref "CN10") (pin "05") (pinfunction "05_05") (pintype "passive"))
    )
    (net (code "83") (name "unconnected-(CN10-Pad06)") (class "Default")
      (node (ref "CN10") (pin "06") (pinfunction "06_06") (pintype "passive"))
    )
    (net (code "84") (name "unconnected-(CN10-Pad07)") (class "Default")
      (node (ref "CN10") (pin "07") (pinfunction "07_07") (pintype "passive"))
    )
    (net (code "85") (name "unconnected-(CN10-Pad08)") (class "Default")
      (node (ref "CN10") (pin "08") (pinfunction "08_08") (pintype "passive"))
    )
    (net (code "86") (name "unconnected-(CN10-Pad09)") (class "Default")
      (node (ref "CN10") (pin "09") (pinfunction "09_09") (pintype "passive"))
    )
    (net (code "87") (name "unconnected-(CN10-Pad10)") (class "Default")
      (node (ref "CN10") (pin "10") (pinfunction "10_10") (pintype "passive"))
    )
    (net (code "88") (name "unconnected-(CN10-Pad12)") (class "Default")
      (node (ref "CN10") (pin "12") (pinfunction "12_12") (pintype "passive"))
    )
    (net (code "89") (name "unconnected-(CN10-Pad14)") (class "Default")
      (node (ref "CN10") (pin "14") (pinfunction "14_14") (pintype "passive"))
    )
    (net (code "90") (name "unconnected-(CN10-Pad17)") (class "Default")
      (node (ref "CN10") (pin "17") (pinfunction "17_17") (pintype "passive"))
    )
    (net (code "91") (name "unconnected-(CN10-Pad19)") (class "Default")
      (node (ref "CN10") (pin "19") (pinfunction "19_19") (pintype "passive"))
    )
    (net (code "92") (name "unconnected-(CN10-Pad21)") (class "Default")
      (node (ref "CN10") (pin "21") (pinfunction "21_21") (pintype "passive"))
    )
    (net (code "93") (name "unconnected-(CN10-Pad23)") (class "Default")
      (node (ref "CN10") (pin "23") (pinfunction "23_23") (pintype "passive"))
    )
    (net (code "94") (name "unconnected-(CN10-Pad24)") (class "Default")
      (node (ref "CN10") (pin "24") (pinfunction "24_24") (pintype "passive"))
    )
    (net (code "95") (name "unconnected-(CN10-Pad26)") (class "Default")
      (node (ref "CN10") (pin "26") (pinfunction "26_26") (pintype "passive"))
    )
    (net (code "96") (name "unconnected-(CN10-Pad28)") (class "Default")
      (node (ref "CN10") (pin "28") (pinfunction "28_28") (pintype "passive"))
    )
    (net (code "97") (name "unconnected-(CN10-Pad31)") (class "Default")
      (node (ref "CN10") (pin "31") (pinfunction "31_31") (pintype "passive"))
    )
    (net (code "98") (name "unconnected-(CN10-Pad33)") (class "Default")
      (node (ref "CN10") (pin "33") (pinfunction "33_33") (pintype "passive"))
    )
    (net (code "99") (name "unconnected-(CN10-Pad35)") (class "Default")
      (node (ref "CN10") (pin "35") (pinfunction "35_35") (pintype "passive"))
    )
    (net (code "100") (name "unconnected-(CN10-Pad36)") (class "Default")
      (node (ref "CN10") (pin "36") (pinfunction "36_36") (pintype "passive"))
    )
    (net (code "101") (name "unconnected-(CN10-Pad37)") (class "Default")
      (node (ref "CN10") (pin "37") (pinfunction "37_37") (pintype "passive"))
    )
    (net (code "102") (name "unconnected-(CN10-Pad38)") (class "Default")
      (node (ref "CN10") (pin "38") (pinfunction "38_38") (pintype "passive"))
    )
    (net (code "103") (name "unconnected-(DRVMOT1_COM-Pad01)") (class "Default")
      (node (ref "DRVMOT1_COM") (pin "01") (pinfunction "01_01") (pintype "passive"))
    )
    (net (code "104") (name "unconnected-(DRVMOT1_COM-Pad05)") (class "Default")
      (node (ref "DRVMOT1_COM") (pin "05") (pinfunction "05_05") (pintype "passive"))
    )
    (net (code "105") (name "unconnected-(DRVMOT1_POW-Pad07)") (class "Default")
      (node (ref "DRVMOT1_POW") (pin "07") (pinfunction "07_07") (pintype "passive"))
    )
    (net (code "106") (name "unconnected-(DRVMOT2_COM-Pad01)") (class "Default")
      (node (ref "DRVMOT2_COM") (pin "01") (pinfunction "01_01") (pintype "passive"))
    )
    (net (code "107") (name "unconnected-(DRVMOT2_COM-Pad05)") (class "Default")
      (node (ref "DRVMOT2_COM") (pin "05") (pinfunction "05_05") (pintype "passive"))
    )
    (net (code "108") (name "unconnected-(DRVMOT2_POW-Pad07)") (class "Default")
      (node (ref "DRVMOT2_POW") (pin "07") (pinfunction "07_07") (pintype "passive"))
    )
    (net (code "109") (name "unconnected-(DRVMOT3_COM-Pad01)") (class "Default")
      (node (ref "DRVMOT3_COM") (pin "01") (pinfunction "01_01") (pintype "passive"))
    )
    (net (code "110") (name "unconnected-(DRVMOT3_COM-Pad05)") (class "Default")
      (node (ref "DRVMOT3_COM") (pin "05") (pinfunction "05_05") (pintype "passive"))
    )
    (net (code "111") (name "unconnected-(DRVMOT3_POW-Pad07)") (class "Default")
      (node (ref "DRVMOT3_POW") (pin "07") (pinfunction "07_07") (pintype "passive"))
    )
    (net (code "112") (name "unconnected-(DRVMOT4_COM-Pad01)") (class "Default")
      (node (ref "DRVMOT4_COM") (pin "01") (pinfunction "01_01") (pintype "passive"))
    )
    (net (code "113") (name "unconnected-(DRVMOT4_COM-Pad05)") (class "Default")
      (node (ref "DRVMOT4_COM") (pin "05") (pinfunction "05_05") (pintype "passive"))
    )
    (net (code "114") (name "unconnected-(DRVMOT4_POW-Pad07)") (class "Default")
      (node (ref "DRVMOT4_POW") (pin "07") (pinfunction "07_07") (pintype "passive"))
    )
  )
)
